# FT2232Circuit.net
KiCad netlist of a schematic drawn in Altium Designer
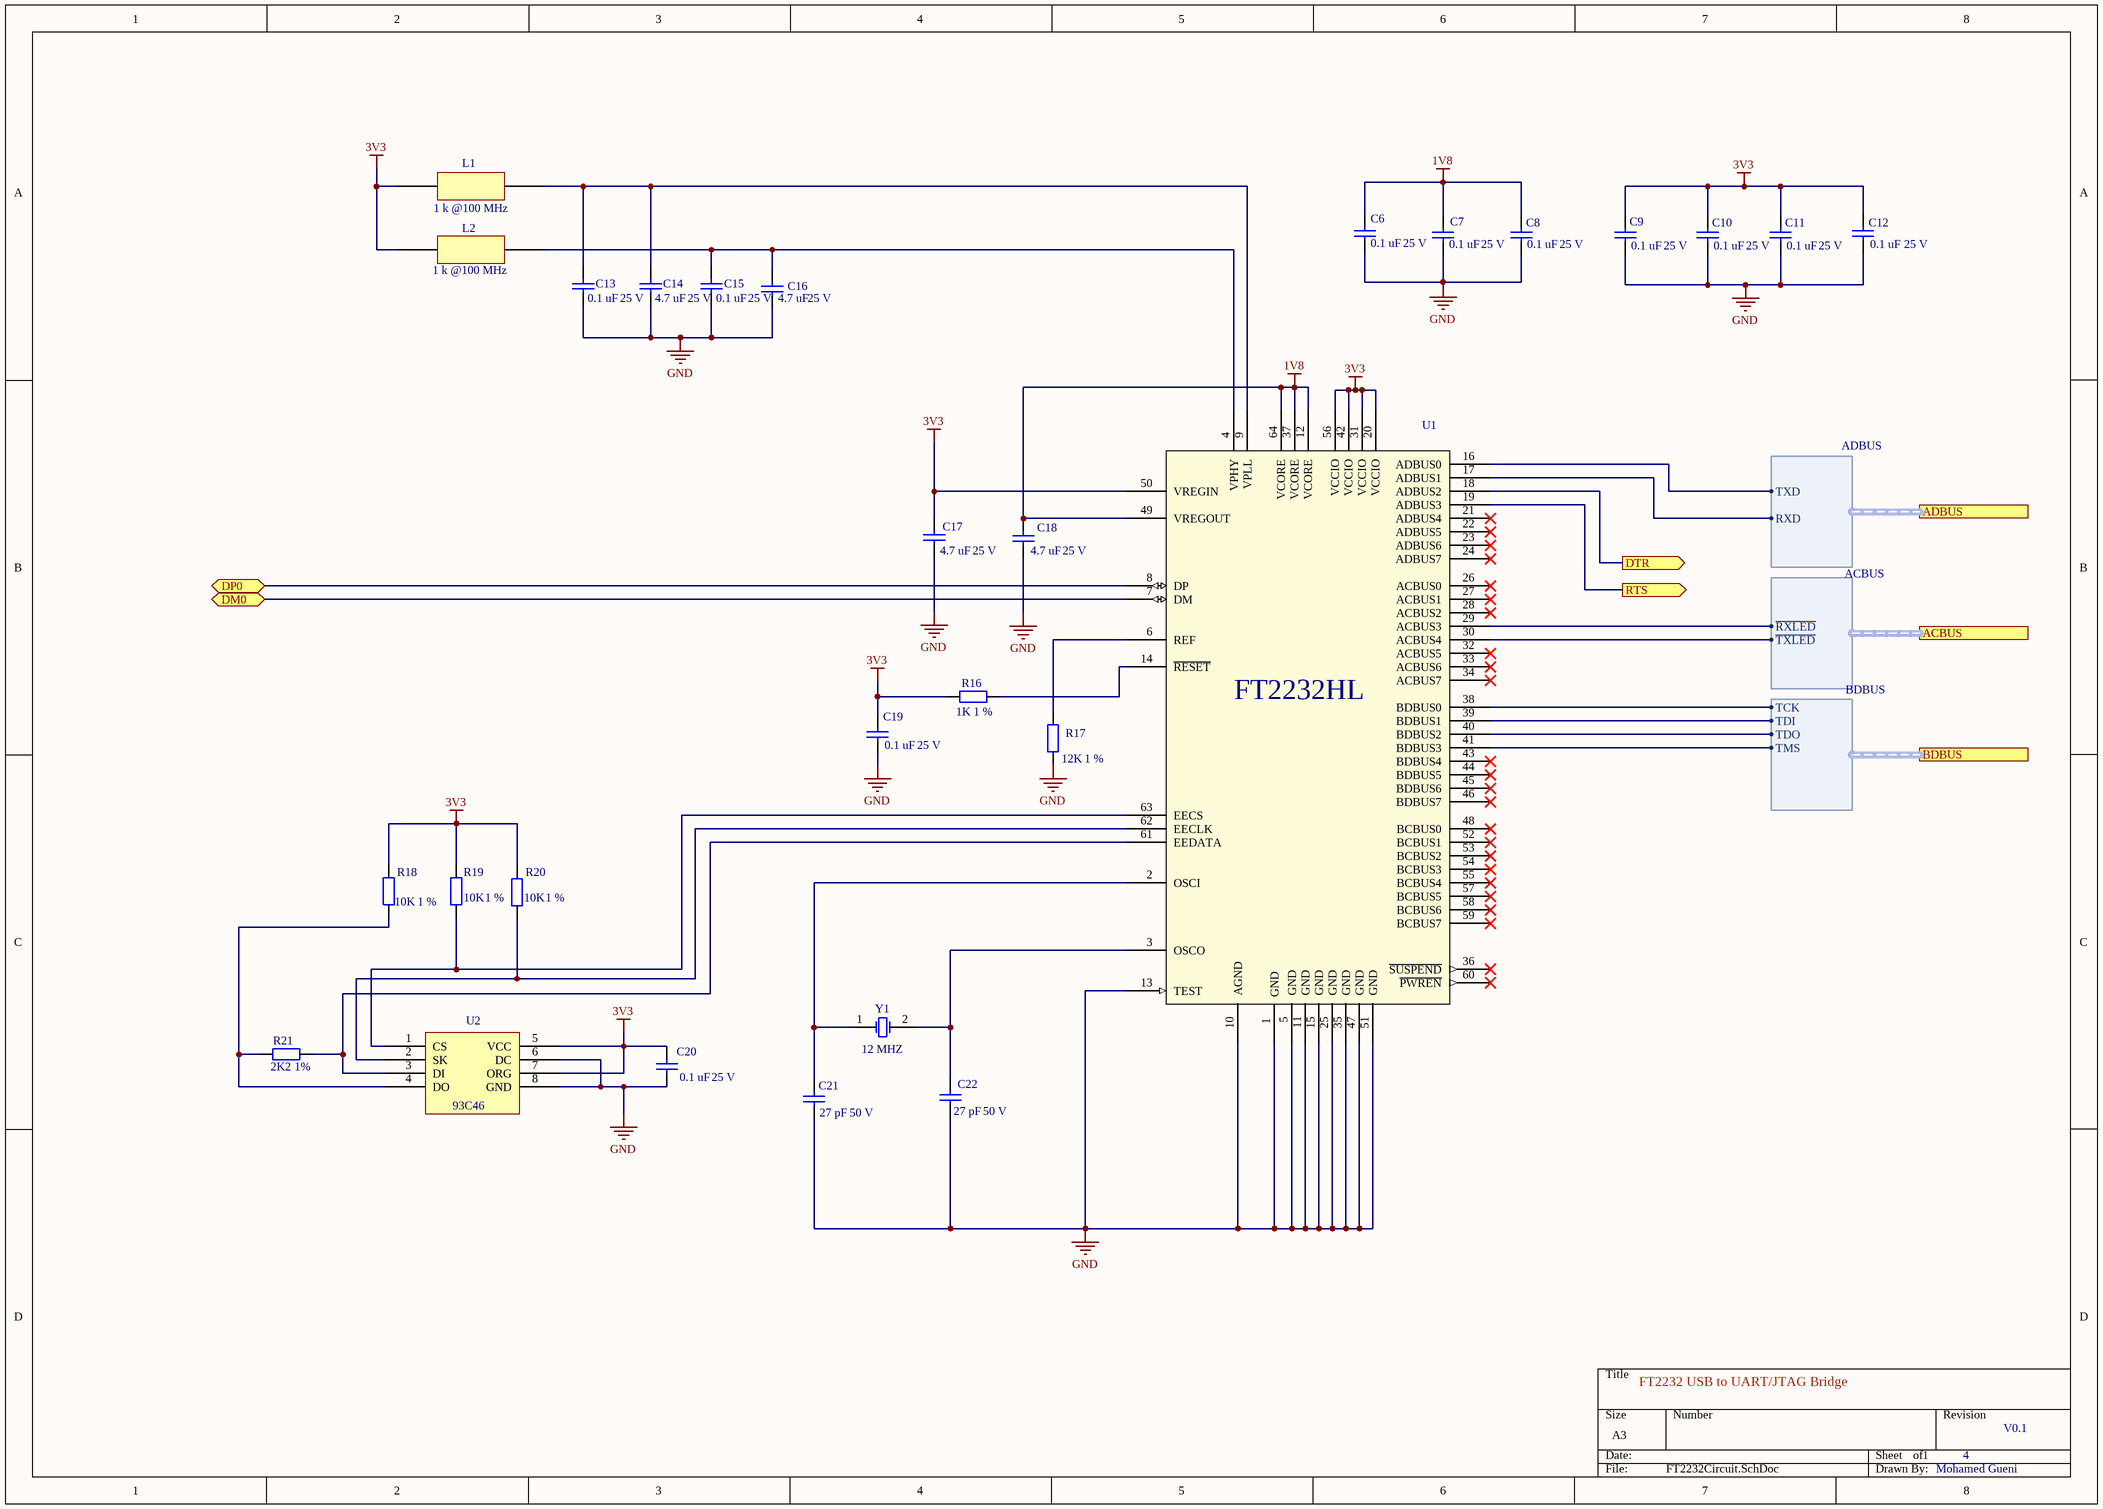
[diagram p0: FT2232Circuit.SchDoc]

(export (version "E")
  (design (tool "Eeschema 10.0.6"))
  (components
    (comp (ref "C6")
      (value "Capacitor")
      (footprint "CAP0603")
      (fields (field (name "VALUE 1") "0.1 uF") (field (name "VALUE 2") "25 V"))
      (libsource (lib "Database_Libs1") (part "Capacitor"))
    )
    (comp (ref "C7")
      (value "Capacitor")
      (footprint "CAP0603")
      (fields (field (name "VALUE 1") "0.1 uF") (field (name "VALUE 2") "25 V"))
      (libsource (lib "Database_Libs1") (part "Capacitor"))
    )
    (comp (ref "C8")
      (value "Capacitor")
      (footprint "CAP0603")
      (fields (field (name "VALUE 1") "0.1 uF") (field (name "VALUE 2") "25 V"))
      (libsource (lib "Database_Libs1") (part "Capacitor"))
    )
    (comp (ref "C9")
      (value "Capacitor")
      (footprint "CAP0603")
      (fields (field (name "VALUE 1") "0.1 uF") (field (name "VALUE 2") "25 V"))
      (libsource (lib "Database_Libs1") (part "Capacitor"))
    )
    (comp (ref "C10")
      (value "Capacitor")
      (footprint "CAP0603")
      (fields (field (name "VALUE 1") "0.1 uF") (field (name "VALUE 2") "25 V"))
      (libsource (lib "Database_Libs1") (part "Capacitor"))
    )
    (comp (ref "C11")
      (value "Capacitor")
      (footprint "CAP0603")
      (fields (field (name "VALUE 1") "0.1 uF") (field (name "VALUE 2") "25 V"))
      (libsource (lib "Database_Libs1") (part "Capacitor"))
    )
    (comp (ref "C12")
      (value "Capacitor")
      (footprint "CAP0603")
      (fields (field (name "VALUE 1") "0.1 uF") (field (name "VALUE 2") "25 V"))
      (libsource (lib "Database_Libs1") (part "Capacitor"))
    )
    (comp (ref "C13")
      (value "Capacitor")
      (footprint "CAP0603")
      (fields (field (name "VALUE 1") "0.1 uF") (field (name "VALUE 2") "25 V"))
      (libsource (lib "Database_Libs1") (part "Capacitor"))
    )
    (comp (ref "C14")
      (value "Capacitor")
      (footprint "CAP0603")
      (fields (field (name "VALUE 1") "4.7 uF") (field (name "VALUE 2") "25 V"))
      (libsource (lib "Database_Libs1") (part "Capacitor"))
    )
    (comp (ref "C15")
      (value "Capacitor")
      (footprint "CAP0603")
      (fields (field (name "VALUE 1") "0.1 uF") (field (name "VALUE 2") "25 V"))
      (libsource (lib "Database_Libs1") (part "Capacitor"))
    )
    (comp (ref "C16")
      (value "Capacitor")
      (footprint "CAP0603")
      (fields (field (name "VALUE 1") "4.7 uF") (field (name "VALUE 2") "25 V"))
      (libsource (lib "Database_Libs1") (part "Capacitor"))
    )
    (comp (ref "C17")
      (value "Capacitor")
      (footprint "CAP0603")
      (fields (field (name "VALUE 1") "4.7 uF") (field (name "VALUE 2") "25 V"))
      (libsource (lib "Database_Libs1") (part "Capacitor"))
    )
    (comp (ref "C18")
      (value "Capacitor")
      (footprint "CAP0603")
      (fields (field (name "VALUE 1") "4.7 uF") (field (name "VALUE 2") "25 V"))
      (libsource (lib "Database_Libs1") (part "Capacitor"))
    )
    (comp (ref "C19")
      (value "Capacitor")
      (footprint "CAP0603")
      (fields (field (name "VALUE 1") "0.1 uF") (field (name "VALUE 2") "25 V"))
      (libsource (lib "Database_Libs1") (part "Capacitor"))
    )
    (comp (ref "C20")
      (value "Capacitor")
      (footprint "CAP0603")
      (fields (field (name "VALUE 1") "0.1 uF") (field (name "VALUE 2") "25 V"))
      (libsource (lib "Database_Libs1") (part "Capacitor"))
    )
    (comp (ref "C21")
      (value "Capacitor")
      (footprint "CAP0603")
      (fields (field (name "VALUE 1") "27 pF") (field (name "VALUE 2") "50 V"))
      (libsource (lib "Database_Libs1") (part "Capacitor"))
    )
    (comp (ref "C22")
      (value "Capacitor")
      (footprint "CAP0603")
      (fields (field (name "VALUE 1") "27 pF") (field (name "VALUE 2") "50 V"))
      (libsource (lib "Database_Libs1") (part "Capacitor"))
    )
    (comp (ref "L1")
      (value "Ferrit Bead")
      (footprint "RESC3216X18N")
      (fields (field (name "VALUE 1") "1 k @100 MHz"))
      (libsource (lib "Database_Libs1") (part "Ferrit Bead"))
    )
    (comp (ref "L2")
      (value "Ferrit Bead")
      (footprint "RESC3216X18N")
      (fields (field (name "VALUE 1") "1 k @100 MHz"))
      (libsource (lib "Database_Libs1") (part "Ferrit Bead"))
    )
    (comp (ref "R16")
      (value "Resistor")
      (footprint "RES0603")
      (fields (field (name "VALUE 1") "1K") (field (name "TOL") "1 %"))
      (libsource (lib "Database_Libs1") (part "Resistor"))
    )
    (comp (ref "R17")
      (value "Resistor")
      (footprint "RES0603")
      (fields (field (name "VALUE 1") "12K") (field (name "TOL") "1 %"))
      (libsource (lib "") (part "Resistor_1"))
    )
    (comp (ref "R18")
      (value "Resistor")
      (footprint "RES0603")
      (fields (field (name "VALUE 1") "10K") (field (name "TOL") "1 %"))
      (libsource (lib "") (part "Resistor_1"))
    )
    (comp (ref "R19")
      (value "Resistor")
      (footprint "RES0603")
      (fields (field (name "VALUE 1") "10K") (field (name "TOL") "1 %"))
      (libsource (lib "") (part "Resistor_1"))
    )
    (comp (ref "R20")
      (value "Resistor")
      (footprint "RES0603")
      (fields (field (name "VALUE 1") "10K") (field (name "TOL") "1 %"))
      (libsource (lib "") (part "Resistor_1"))
    )
    (comp (ref "R21")
      (value "Resistor")
      (footprint "RES0603")
      (fields (field (name "VALUE 1") "2K2") (field (name "TOL") "1%"))
      (libsource (lib "Database_Libs1") (part "Resistor"))
    )
    (comp (ref "U1")
      (value "FT2232HL-REEL")
      (footprint "TSQFP50P1200X1200X160-64N")
      (description "IC USB HS DUAL UART/FIFO 64-LQFP")
      (libsource (lib "Database_Libs1") (part "FT2232HL-REEL"))
    )
    (comp (ref "U2")
      (value "93C46")
      (footprint "SOIC127P600X175-8N")
      (description "EEPROM 64x16")
      (libsource (lib "Database_Libs1") (part "93C46"))
    )
    (comp (ref "Y1")
      (value "XTAL")
      (footprint "ABLS-12.000MHZ-B2")
      (description "Crystal Oscillator")
      (fields (field (name "VALUE 1") "12 MHZ") (field (name "PUBLISHER") "Altium Limited"))
      (libsource (lib "Database_Libs1") (part "XTAL"))
    )
  )
  (nets
    (net (code "4") (name "/DM0") (class "Default")
      (node (ref "U1") (pin "7") (pinfunction "DM_7") (pintype "bidirectional"))
    )
    (net (code "5") (name "/DP0") (class "Default")
      (node (ref "U1") (pin "8") (pinfunction "DP_8") (pintype "bidirectional"))
    )
    (net (code "6") (name "/DTR") (class "Default")
      (node (ref "U1") (pin "18") (pinfunction "ADBUS2_18") (pintype "passive"))
    )
    (net (code "7") (name "/RTS") (class "Default")
      (node (ref "U1") (pin "19") (pinfunction "ADBUS3_19") (pintype "passive"))
    )
    (net (code "8") (name "/RXD") (class "Default")
      (node (ref "U1") (pin "17") (pinfunction "ADBUS1_17") (pintype "passive"))
    )
    (net (code "9") (name "/TCK") (class "Default")
      (node (ref "U1") (pin "38") (pinfunction "BDBUS0_38") (pintype "passive"))
    )
    (net (code "10") (name "/TDI") (class "Default")
      (node (ref "U1") (pin "39") (pinfunction "BDBUS1_39") (pintype "passive"))
    )
    (net (code "11") (name "/TDO") (class "Default")
      (node (ref "U1") (pin "40") (pinfunction "BDBUS2_40") (pintype "passive"))
    )
    (net (code "12") (name "/TMS") (class "Default")
      (node (ref "U1") (pin "41") (pinfunction "BDBUS3_41") (pintype "passive"))
    )
    (net (code "13") (name "/TXD") (class "Default")
      (node (ref "U1") (pin "16") (pinfunction "ADBUS0_16") (pintype "passive"))
    )
    (net (code "17") (name "/~{RXLED}") (class "Default")
      (node (ref "U1") (pin "29") (pinfunction "ACBUS3_29") (pintype "passive"))
    )
    (net (code "18") (name "/~{TXLED}") (class "Default")
      (node (ref "U1") (pin "30") (pinfunction "ACBUS4_30") (pintype "passive"))
    )
    (net (code "19") (name "1V8") (class "Default")
      (node (ref "C18") (pin "2") (pinfunction "2_2") (pintype "passive"))
      (node (ref "C6") (pin "2") (pinfunction "2_2") (pintype "passive"))
      (node (ref "C7") (pin "2") (pinfunction "2_2") (pintype "passive"))
      (node (ref "C8") (pin "2") (pinfunction "2_2") (pintype "passive"))
      (node (ref "U1") (pin "12") (pinfunction "VCORE_12") (pintype "power_in"))
      (node (ref "U1") (pin "37") (pinfunction "VCORE_37") (pintype "power_in"))
      (node (ref "U1") (pin "49") (pinfunction "VREGOUT_49") (pintype "power_in"))
      (node (ref "U1") (pin "64") (pinfunction "VCORE_64") (pintype "power_in"))
    )
    (net (code "20") (name "3V3") (class "Default")
      (node (ref "C10") (pin "2") (pinfunction "2_2") (pintype "passive"))
      (node (ref "C11") (pin "2") (pinfunction "2_2") (pintype "passive"))
      (node (ref "C12") (pin "2") (pinfunction "2_2") (pintype "passive"))
      (node (ref "C17") (pin "2") (pinfunction "2_2") (pintype "passive"))
      (node (ref "C19") (pin "2") (pinfunction "2_2") (pintype "passive"))
      (node (ref "C20") (pin "2") (pinfunction "2_2") (pintype "passive"))
      (node (ref "C9") (pin "2") (pinfunction "2_2") (pintype "passive"))
      (node (ref "L1") (pin "2") (pinfunction "2_2") (pintype "passive"))
      (node (ref "L2") (pin "2") (pinfunction "2_2") (pintype "passive"))
      (node (ref "R16") (pin "1") (pinfunction "1_1") (pintype "passive"))
      (node (ref "R18") (pin "2") (pinfunction "2_2") (pintype "passive"))
      (node (ref "R19") (pin "2") (pinfunction "2_2") (pintype "passive"))
      (node (ref "R20") (pin "2") (pinfunction "2_2") (pintype "passive"))
      (node (ref "U1") (pin "20") (pinfunction "VCCIO_20") (pintype "power_in"))
      (node (ref "U1") (pin "31") (pinfunction "VCCIO_31") (pintype "power_in"))
      (node (ref "U1") (pin "42") (pinfunction "VCCIO_42") (pintype "power_in"))
      (node (ref "U1") (pin "50") (pinfunction "VREGIN_50") (pintype "power_in"))
      (node (ref "U1") (pin "56") (pinfunction "VCCIO_56") (pintype "power_in"))
      (node (ref "U2") (pin "5") (pinfunction "VCC_5") (pintype "power_in"))
      (node (ref "U2") (pin "7") (pinfunction "ORG_7") (pintype "passive"))
    )
    (net (code "21") (name "GND") (class "Default")
      (node (ref "C10") (pin "1") (pinfunction "1_1") (pintype "passive"))
      (node (ref "C11") (pin "1") (pinfunction "1_1") (pintype "passive"))
      (node (ref "C12") (pin "1") (pinfunction "1_1") (pintype "passive"))
      (node (ref "C13") (pin "1") (pinfunction "1_1") (pintype "passive"))
      (node (ref "C14") (pin "1") (pinfunction "1_1") (pintype "passive"))
      (node (ref "C15") (pin "1") (pinfunction "1_1") (pintype "passive"))
      (node (ref "C16") (pin "1") (pinfunction "1_1") (pintype "passive"))
      (node (ref "C17") (pin "1") (pinfunction "1_1") (pintype "passive"))
      (node (ref "C18") (pin "1") (pinfunction "1_1") (pintype "passive"))
      (node (ref "C19") (pin "1") (pinfunction "1_1") (pintype "passive"))
      (node (ref "C20") (pin "1") (pinfunction "1_1") (pintype "passive"))
      (node (ref "C21") (pin "1") (pinfunction "1_1") (pintype "passive"))
      (node (ref "C22") (pin "1") (pinfunction "1_1") (pintype "passive"))
      (node (ref "C6") (pin "1") (pinfunction "1_1") (pintype "passive"))
      (node (ref "C7") (pin "1") (pinfunction "1_1") (pintype "passive"))
      (node (ref "C8") (pin "1") (pinfunction "1_1") (pintype "passive"))
      (node (ref "C9") (pin "1") (pinfunction "1_1") (pintype "passive"))
      (node (ref "R17") (pin "1") (pinfunction "1_1") (pintype "passive"))
      (node (ref "U1") (pin "1") (pinfunction "GND_1") (pintype "power_in"))
      (node (ref "U1") (pin "10") (pinfunction "AGND_10") (pintype "power_in"))
      (node (ref "U1") (pin "11") (pinfunction "GND_11") (pintype "power_in"))
      (node (ref "U1") (pin "13") (pinfunction "TEST_13") (pintype "input"))
      (node (ref "U1") (pin "15") (pinfunction "GND_15") (pintype "power_in"))
      (node (ref "U1") (pin "25") (pinfunction "GND_25") (pintype "power_in"))
      (node (ref "U1") (pin "35") (pinfunction "GND_35") (pintype "power_in"))
      (node (ref "U1") (pin "47") (pinfunction "GND_47") (pintype "power_in"))
      (node (ref "U1") (pin "5") (pinfunction "GND_5") (pintype "power_in"))
      (node (ref "U1") (pin "51") (pinfunction "GND_51") (pintype "power_in"))
      (node (ref "U2") (pin "6") (pinfunction "DC_6") (pintype "passive"))
      (node (ref "U2") (pin "8") (pinfunction "GND_8") (pintype "power_in"))
    )
    (net (code "22") (name "Net-(U1-EECLK)") (class "Default")
      (node (ref "R20") (pin "1") (pinfunction "1_1") (pintype "passive"))
      (node (ref "U1") (pin "62") (pinfunction "EECLK_62") (pintype "passive"))
      (node (ref "U2") (pin "2") (pinfunction "SK_2") (pintype "passive"))
    )
    (net (code "23") (name "Net-(U1-EECS)") (class "Default")
      (node (ref "R19") (pin "1") (pinfunction "1_1") (pintype "passive"))
      (node (ref "U1") (pin "63") (pinfunction "EECS_63") (pintype "passive"))
      (node (ref "U2") (pin "1") (pinfunction "CS_1") (pintype "passive"))
    )
    (net (code "24") (name "Net-(U1-EEDATA)") (class "Default")
      (node (ref "R21") (pin "2") (pinfunction "2_2") (pintype "passive"))
      (node (ref "U1") (pin "61") (pinfunction "EEDATA_61") (pintype "passive"))
      (node (ref "U2") (pin "3") (pinfunction "DI_3") (pintype "passive"))
    )
    (net (code "25") (name "Net-(U1-OSCI)") (class "Default")
      (node (ref "C21") (pin "2") (pinfunction "2_2") (pintype "passive"))
      (node (ref "U1") (pin "2") (pinfunction "OSCI_2") (pintype "passive"))
      (node (ref "Y1") (pin "1") (pinfunction "OSC1_1") (pintype "passive"))
    )
    (net (code "26") (name "Net-(U1-OSCO)") (class "Default")
      (node (ref "C22") (pin "2") (pinfunction "2_2") (pintype "passive"))
      (node (ref "U1") (pin "3") (pinfunction "OSCO_3") (pintype "passive"))
      (node (ref "Y1") (pin "2") (pinfunction "OSC2_2") (pintype "passive"))
    )
    (net (code "27") (name "Net-(U1-REF)") (class "Default")
      (node (ref "R17") (pin "2") (pinfunction "2_2") (pintype "passive"))
      (node (ref "U1") (pin "6") (pinfunction "REF_6") (pintype "passive"))
    )
    (net (code "28") (name "Net-(U1-VPHY)") (class "Default")
      (node (ref "C15") (pin "2") (pinfunction "2_2") (pintype "passive"))
      (node (ref "C16") (pin "2") (pinfunction "2_2") (pintype "passive"))
      (node (ref "L2") (pin "1") (pinfunction "1_1") (pintype "passive"))
      (node (ref "U1") (pin "4") (pinfunction "VPHY_4") (pintype "power_in"))
    )
    (net (code "29") (name "Net-(U1-VPLL)") (class "Default")
      (node (ref "C13") (pin "2") (pinfunction "2_2") (pintype "passive"))
      (node (ref "C14") (pin "2") (pinfunction "2_2") (pintype "passive"))
      (node (ref "L1") (pin "1") (pinfunction "1_1") (pintype "passive"))
      (node (ref "U1") (pin "9") (pinfunction "VPLL_9") (pintype "power_in"))
    )
    (net (code "30") (name "Net-(U1-~{RESET})") (class "Default")
      (node (ref "R16") (pin "2") (pinfunction "2_2") (pintype "passive"))
      (node (ref "U1") (pin "14") (pinfunction "~{RESET}_14") (pintype "passive"))
    )
    (net (code "31") (name "Net-(U2-DO)") (class "Default")
      (node (ref "R18") (pin "1") (pinfunction "1_1") (pintype "passive"))
      (node (ref "R21") (pin "1") (pinfunction "1_1") (pintype "passive"))
      (node (ref "U2") (pin "4") (pinfunction "DO_4") (pintype "passive"))
    )
    (net (code "32") (name "unconnected-(U1-ACBUS0-Pad26)") (class "Default")
      (node (ref "U1") (pin "26") (pinfunction "ACBUS0_26") (pintype "passive+no_connect"))
    )
    (net (code "33") (name "unconnected-(U1-ACBUS1-Pad27)") (class "Default")
      (node (ref "U1") (pin "27") (pinfunction "ACBUS1_27") (pintype "passive+no_connect"))
    )
    (net (code "34") (name "unconnected-(U1-ACBUS2-Pad28)") (class "Default")
      (node (ref "U1") (pin "28") (pinfunction "ACBUS2_28") (pintype "passive+no_connect"))
    )
    (net (code "35") (name "unconnected-(U1-ACBUS5-Pad32)") (class "Default")
      (node (ref "U1") (pin "32") (pinfunction "ACBUS5_32") (pintype "passive+no_connect"))
    )
    (net (code "36") (name "unconnected-(U1-ACBUS6-Pad33)") (class "Default")
      (node (ref "U1") (pin "33") (pinfunction "ACBUS6_33") (pintype "passive+no_connect"))
    )
    (net (code "37") (name "unconnected-(U1-ACBUS7-Pad34)") (class "Default")
      (node (ref "U1") (pin "34") (pinfunction "ACBUS7_34") (pintype "passive+no_connect"))
    )
    (net (code "38") (name "unconnected-(U1-ADBUS4-Pad21)") (class "Default")
      (node (ref "U1") (pin "21") (pinfunction "ADBUS4_21") (pintype "passive+no_connect"))
    )
    (net (code "39") (name "unconnected-(U1-ADBUS5-Pad22)") (class "Default")
      (node (ref "U1") (pin "22") (pinfunction "ADBUS5_22") (pintype "passive+no_connect"))
    )
    (net (code "40") (name "unconnected-(U1-ADBUS6-Pad23)") (class "Default")
      (node (ref "U1") (pin "23") (pinfunction "ADBUS6_23") (pintype "passive+no_connect"))
    )
    (net (code "41") (name "unconnected-(U1-ADBUS7-Pad24)") (class "Default")
      (node (ref "U1") (pin "24") (pinfunction "ADBUS7_24") (pintype "passive+no_connect"))
    )
    (net (code "42") (name "unconnected-(U1-BCBUS0-Pad48)") (class "Default")
      (node (ref "U1") (pin "48") (pinfunction "BCBUS0_48") (pintype "passive+no_connect"))
    )
    (net (code "43") (name "unconnected-(U1-BCBUS1-Pad52)") (class "Default")
      (node (ref "U1") (pin "52") (pinfunction "BCBUS1_52") (pintype "passive+no_connect"))
    )
    (net (code "44") (name "unconnected-(U1-BCBUS2-Pad53)") (class "Default")
      (node (ref "U1") (pin "53") (pinfunction "BCBUS2_53") (pintype "passive+no_connect"))
    )
    (net (code "45") (name "unconnected-(U1-BCBUS3-Pad54)") (class "Default")
      (node (ref "U1") (pin "54") (pinfunction "BCBUS3_54") (pintype "passive+no_connect"))
    )
    (net (code "46") (name "unconnected-(U1-BCBUS4-Pad55)") (class "Default")
      (node (ref "U1") (pin "55") (pinfunction "BCBUS4_55") (pintype "passive+no_connect"))
    )
    (net (code "47") (name "unconnected-(U1-BCBUS5-Pad57)") (class "Default")
      (node (ref "U1") (pin "57") (pinfunction "BCBUS5_57") (pintype "passive+no_connect"))
    )
    (net (code "48") (name "unconnected-(U1-BCBUS6-Pad58)") (class "Default")
      (node (ref "U1") (pin "58") (pinfunction "BCBUS6_58") (pintype "passive+no_connect"))
    )
    (net (code "49") (name "unconnected-(U1-BCBUS7-Pad59)") (class "Default")
      (node (ref "U1") (pin "59") (pinfunction "BCBUS7_59") (pintype "passive+no_connect"))
    )
    (net (code "50") (name "unconnected-(U1-BDBUS4-Pad43)") (class "Default")
      (node (ref "U1") (pin "43") (pinfunction "BDBUS4_43") (pintype "passive+no_connect"))
    )
    (net (code "51") (name "unconnected-(U1-BDBUS5-Pad44)") (class "Default")
      (node (ref "U1") (pin "44") (pinfunction "BDBUS5_44") (pintype "passive+no_connect"))
    )
    (net (code "52") (name "unconnected-(U1-BDBUS6-Pad45)") (class "Default")
      (node (ref "U1") (pin "45") (pinfunction "BDBUS6_45") (pintype "passive+no_connect"))
    )
    (net (code "53") (name "unconnected-(U1-BDBUS7-Pad46)") (class "Default")
      (node (ref "U1") (pin "46") (pinfunction "BDBUS7_46") (pintype "passive+no_connect"))
    )
    (net (code "54") (name "unconnected-(U1-~{PWREN}-Pad60)") (class "Default")
      (node (ref "U1") (pin "60") (pinfunction "~{PWREN}_60") (pintype "output+no_connect"))
    )
    (net (code "55") (name "unconnected-(U1-~{SUSPEND}-Pad36)") (class "Default")
      (node (ref "U1") (pin "36") (pinfunction "~{SUSPEND}_36") (pintype "output+no_connect"))
    )
  )
)
